# AD5933_Breakout.net
KiCad netlist of a schematic drawn in EAGLE
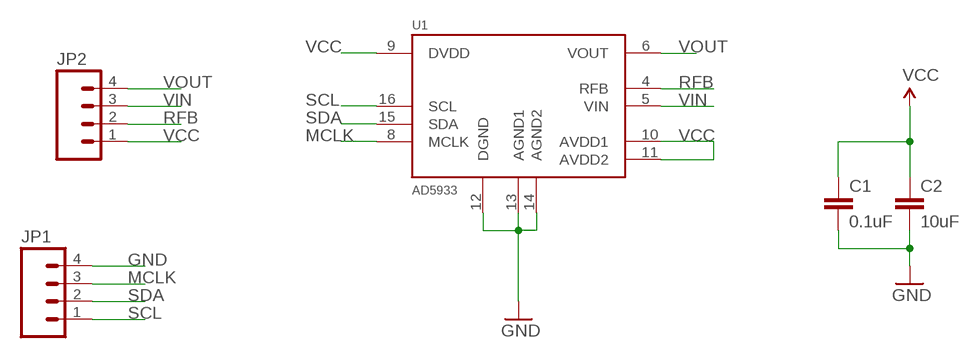
[diagram p0: schematic, sheet 1]

(export (version "E")
  (design (tool "Eeschema 10.0.6"))
  (components
    (comp (ref "C1")
      (value "0.1uF")
      (footprint "eagle-import:0603-CAP")
      (libsource (lib "eagle-import") (part "0.1UF-100V-10%(0603)"))
    )
    (comp (ref "C2")
      (value "10uF")
      (footprint "eagle-import:0603-CAP")
      (libsource (lib "eagle-import") (part "0.1UF-100V-10%(0603)"))
    )
    (comp (ref "JP1")
      (value "M04PTH")
      (footprint "eagle-import:1X04")
      (libsource (lib "eagle-import") (part "M04PTH"))
    )
    (comp (ref "JP2")
      (value "M04PTH")
      (footprint "eagle-import:1X04")
      (libsource (lib "eagle-import") (part "M04PTH"))
    )
    (comp (ref "U1")
      (value "AD5933")
      (footprint "eagle-import:SSOP16")
      (libsource (lib "eagle-import") (part "AD5933"))
    )
  )
  (nets
    (net (code "1") (name "/MCLK") (class "Default")
      (node (ref "JP1") (pin "3") (pinfunction "3_3") (pintype "passive"))
      (node (ref "U1") (pin "8") (pinfunction "MCLK_8") (pintype "bidirectional"))
    )
    (net (code "2") (name "/RFB") (class "Default")
      (node (ref "JP2") (pin "2") (pinfunction "2_2") (pintype "passive"))
      (node (ref "U1") (pin "4") (pinfunction "RFB_4") (pintype "bidirectional"))
    )
    (net (code "3") (name "/SCL") (class "Default")
      (node (ref "JP1") (pin "1") (pinfunction "1_1") (pintype "passive"))
      (node (ref "U1") (pin "16") (pinfunction "SCL_16") (pintype "bidirectional"))
    )
    (net (code "4") (name "/SDA") (class "Default")
      (node (ref "JP1") (pin "2") (pinfunction "2_2") (pintype "passive"))
      (node (ref "U1") (pin "15") (pinfunction "SDA_15") (pintype "bidirectional"))
    )
    (net (code "5") (name "/VIN") (class "Default")
      (node (ref "JP2") (pin "3") (pinfunction "3_3") (pintype "passive"))
      (node (ref "U1") (pin "5") (pinfunction "VIN_5") (pintype "bidirectional"))
    )
    (net (code "6") (name "/VOUT") (class "Default")
      (node (ref "JP2") (pin "4") (pinfunction "4_4") (pintype "passive"))
      (node (ref "U1") (pin "6") (pinfunction "VOUT_6") (pintype "bidirectional"))
    )
    (net (code "7") (name "GND") (class "Default")
      (node (ref "C1") (pin "2") (pinfunction "2_2") (pintype "passive"))
      (node (ref "C2") (pin "2") (pinfunction "2_2") (pintype "passive"))
      (node (ref "JP1") (pin "4") (pinfunction "4_4") (pintype "passive"))
      (node (ref "U1") (pin "12") (pinfunction "DGND_12") (pintype "bidirectional"))
      (node (ref "U1") (pin "13") (pinfunction "AGND1_13") (pintype "bidirectional"))
      (node (ref "U1") (pin "14") (pinfunction "AGND2_14") (pintype "bidirectional"))
    )
    (net (code "8") (name "VCC") (class "Default")
      (node (ref "C1") (pin "1") (pinfunction "1_1") (pintype "passive"))
      (node (ref "C2") (pin "1") (pinfunction "1_1") (pintype "passive"))
      (node (ref "JP2") (pin "1") (pinfunction "1_1") (pintype "passive"))
      (node (ref "U1") (pin "10") (pinfunction "AVDD1_10") (pintype "bidirectional"))
      (node (ref "U1") (pin "11") (pinfunction "AVDD2_11") (pintype "bidirectional"))
      (node (ref "U1") (pin "9") (pinfunction "DVDD_9") (pintype "bidirectional"))
    )
  )
)
